# Hotec_H-bridge.net
KiCad netlist of a schematic drawn in EAGLE
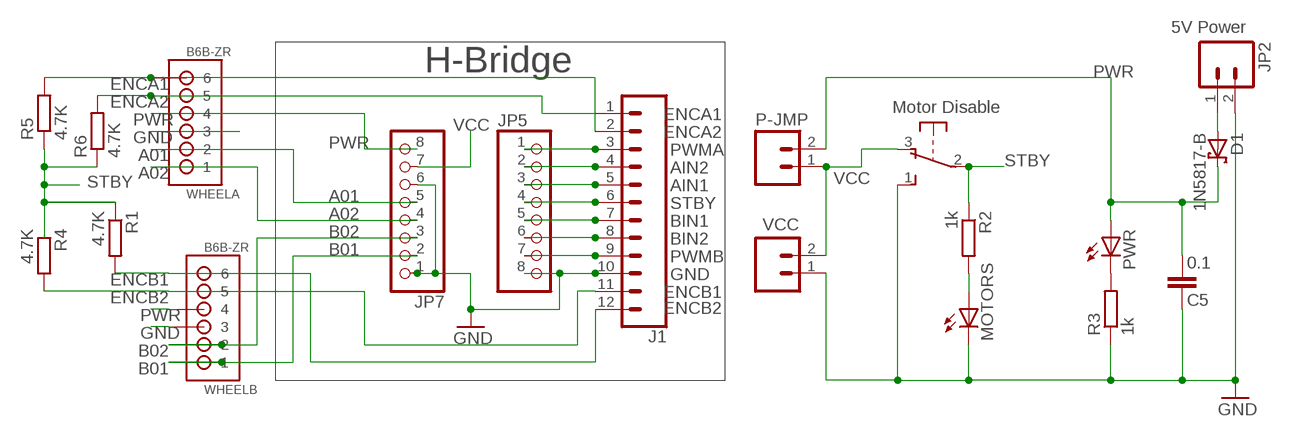
[diagram p0: schematic, sheet 1]

(export (version "E")
  (design (tool "Eeschema 10.0.6"))
  (components
    (comp (ref "C5")
      (value "0.1")
      (footprint "eagle-import:CAP-PTH-SMALLEZ")
      (libsource (lib "eagle-import") (part "CAPEZ"))
    )
    (comp (ref "D1")
      (value "1N5817-B")
      (footprint "eagle-import:DO41-7.6")
      (libsource (lib "eagle-import") (part "1N5817-B"))
    )
    (comp (ref "J1")
      (value "CONN_12")
      (footprint "eagle-import:1X12")
      (libsource (lib "eagle-import") (part "CONN_12"))
    )
    (comp (ref "JP2")
      (value "M023.5MM")
      (footprint "eagle-import:SCREWTERMINAL-3.5MM-2")
      (libsource (lib "eagle-import") (part "M023.5MM"))
    )
    (comp (ref "JP5")
      (value "PINHD-1X8CLEANBIG")
      (footprint "eagle-import:1X08-CLEANBIG")
      (libsource (lib "eagle-import") (part "PINHD-1X8CLEANBIG"))
    )
    (comp (ref "JP7")
      (value "PINHD-1X8CLEANBIG")
      (footprint "eagle-import:1X08-CLEANBIG")
      (libsource (lib "eagle-import") (part "PINHD-1X8CLEANBIG"))
    )
    (comp (ref "MOTORS")
      (value "LED3MM")
      (footprint "eagle-import:LED3MM")
      (libsource (lib "eagle-import") (part "LED3MM"))
    )
    (comp (ref "P-JMP")
      (value "M02PTH")
      (footprint "eagle-import:1X02")
      (libsource (lib "eagle-import") (part "M02PTH"))
    )
    (comp (ref "PWR")
      (value "LED3MM")
      (footprint "eagle-import:LED3MM")
      (libsource (lib "eagle-import") (part "LED3MM"))
    )
    (comp (ref "R1")
      (value "4.7K")
      (footprint "eagle-import:0204_7")
      (libsource (lib "eagle-import") (part "R-EU_0204/7"))
    )
    (comp (ref "R2")
      (value "1k")
      (footprint "eagle-import:0204_7")
      (libsource (lib "eagle-import") (part "R-EU_0204/7"))
    )
    (comp (ref "R3")
      (value "1k")
      (footprint "eagle-import:0204_7")
      (libsource (lib "eagle-import") (part "R-EU_0204/7"))
    )
    (comp (ref "R4")
      (value "4.7K")
      (footprint "eagle-import:0204_7")
      (libsource (lib "eagle-import") (part "R-EU_0204/7"))
    )
    (comp (ref "R5")
      (value "4.7K")
      (footprint "eagle-import:0204_7")
      (libsource (lib "eagle-import") (part "R-EU_0204/7"))
    )
    (comp (ref "R6")
      (value "4.7K")
      (footprint "eagle-import:0204_7")
      (libsource (lib "eagle-import") (part "R-EU_0204/7"))
    )
    (comp (ref "SW1")
      (value "OS102011MA1Q")
      (footprint "eagle-import:OS102011MA1Q")
      (libsource (lib "eagle-import") (part "OS102011MA1Q"))
    )
    (comp (ref "VCC")
      (value "M02PTH")
      (footprint "eagle-import:1X02")
      (libsource (lib "eagle-import") (part "M02PTH"))
    )
    (comp (ref "WHEELA")
      (value "B6B-ZR")
      (footprint "eagle-import:B6B-ZR")
      (libsource (lib "eagle-import") (part "B6B-ZR"))
    )
    (comp (ref "WHEELB")
      (value "B6B-ZR")
      (footprint "eagle-import:B6B-ZR")
      (libsource (lib "eagle-import") (part "B6B-ZR"))
    )
  )
  (nets
    (net (code "1") (name "/A01") (class "Default")
      (node (ref "JP7") (pin "5") (pinfunction "5_5") (pintype "passive"))
      (node (ref "WHEELA") (pin "2") (pinfunction "2_2") (pintype "bidirectional"))
    )
    (net (code "2") (name "/A02") (class "Default")
      (node (ref "JP7") (pin "4") (pinfunction "4_4") (pintype "passive"))
      (node (ref "WHEELA") (pin "1") (pinfunction "1_1") (pintype "bidirectional"))
    )
    (net (code "3") (name "/AIN1") (class "Default")
      (node (ref "J1") (pin "5") (pinfunction "5_5") (pintype "passive"))
      (node (ref "JP5") (pin "3") (pinfunction "3_3") (pintype "passive"))
    )
    (net (code "4") (name "/AIN2") (class "Default")
      (node (ref "J1") (pin "4") (pinfunction "4_4") (pintype "passive"))
      (node (ref "JP5") (pin "2") (pinfunction "2_2") (pintype "passive"))
    )
    (net (code "5") (name "/B01") (class "Default")
      (node (ref "JP7") (pin "2") (pinfunction "2_2") (pintype "passive"))
      (node (ref "WHEELB") (pin "1") (pinfunction "1_1") (pintype "bidirectional"))
    )
    (net (code "6") (name "/B02") (class "Default")
      (node (ref "JP7") (pin "3") (pinfunction "3_3") (pintype "passive"))
      (node (ref "WHEELB") (pin "2") (pinfunction "2_2") (pintype "bidirectional"))
    )
    (net (code "7") (name "/BIN1") (class "Default")
      (node (ref "J1") (pin "7") (pinfunction "7_7") (pintype "passive"))
      (node (ref "JP5") (pin "5") (pinfunction "5_5") (pintype "passive"))
    )
    (net (code "8") (name "/BIN2") (class "Default")
      (node (ref "J1") (pin "8") (pinfunction "8_8") (pintype "passive"))
      (node (ref "JP5") (pin "6") (pinfunction "6_6") (pintype "passive"))
    )
    (net (code "9") (name "/ENCA1") (class "Default")
      (node (ref "J1") (pin "2") (pinfunction "2_2") (pintype "passive"))
      (node (ref "R5") (pin "2") (pinfunction "2_2") (pintype "passive"))
      (node (ref "WHEELA") (pin "6") (pinfunction "6_6") (pintype "bidirectional"))
    )
    (net (code "10") (name "/ENCA2") (class "Default")
      (node (ref "J1") (pin "1") (pinfunction "1_1") (pintype "passive"))
      (node (ref "R6") (pin "2") (pinfunction "2_2") (pintype "passive"))
      (node (ref "WHEELA") (pin "5") (pinfunction "5_5") (pintype "bidirectional"))
    )
    (net (code "11") (name "/ENCB1") (class "Default")
      (node (ref "J1") (pin "12") (pinfunction "12_12") (pintype "passive"))
      (node (ref "R1") (pin "2") (pinfunction "2_2") (pintype "passive"))
      (node (ref "WHEELB") (pin "6") (pinfunction "6_6") (pintype "bidirectional"))
    )
    (net (code "12") (name "/ENCB2") (class "Default")
      (node (ref "J1") (pin "11") (pinfunction "11_11") (pintype "passive"))
      (node (ref "R4") (pin "2") (pinfunction "2_2") (pintype "passive"))
      (node (ref "WHEELB") (pin "5") (pinfunction "5_5") (pintype "bidirectional"))
    )
    (net (code "13") (name "/PWMA") (class "Default")
      (node (ref "J1") (pin "3") (pinfunction "3_3") (pintype "passive"))
      (node (ref "JP5") (pin "1") (pinfunction "1_1") (pintype "passive"))
    )
    (net (code "14") (name "/PWMB") (class "Default")
      (node (ref "J1") (pin "9") (pinfunction "9_9") (pintype "passive"))
      (node (ref "JP5") (pin "7") (pinfunction "7_7") (pintype "passive"))
    )
    (net (code "15") (name "/PWR") (class "Default")
      (node (ref "C5") (pin "2") (pinfunction "2_2") (pintype "passive"))
      (node (ref "D1") (pin "C") (pinfunction "C_C") (pintype "passive"))
      (node (ref "JP7") (pin "8") (pinfunction "8_8") (pintype "passive"))
      (node (ref "P-JMP") (pin "2") (pinfunction "2_2") (pintype "passive"))
      (node (ref "PWR") (pin "A") (pinfunction "A_A") (pintype "passive"))
      (node (ref "WHEELA") (pin "4") (pinfunction "4_4") (pintype "bidirectional"))
      (node (ref "WHEELB") (pin "4") (pinfunction "4_4") (pintype "bidirectional"))
    )
    (net (code "16") (name "/STBY") (class "Default")
      (node (ref "J1") (pin "6") (pinfunction "6_6") (pintype "passive"))
      (node (ref "JP5") (pin "4") (pinfunction "4_4") (pintype "passive"))
      (node (ref "R1") (pin "1") (pinfunction "1_1") (pintype "passive"))
      (node (ref "R2") (pin "1") (pinfunction "1_1") (pintype "passive"))
      (node (ref "R4") (pin "1") (pinfunction "1_1") (pintype "passive"))
      (node (ref "R5") (pin "1") (pinfunction "1_1") (pintype "passive"))
      (node (ref "R6") (pin "1") (pinfunction "1_1") (pintype "passive"))
      (node (ref "SW1") (pin "2") (pinfunction "P_2") (pintype "passive"))
    )
    (net (code "17") (name "/VCC") (class "Default")
      (node (ref "JP7") (pin "7") (pinfunction "7_7") (pintype "passive"))
      (node (ref "P-JMP") (pin "1") (pinfunction "1_1") (pintype "passive"))
      (node (ref "SW1") (pin "3") (pinfunction "O_3") (pintype "passive"))
      (node (ref "VCC") (pin "2") (pinfunction "2_2") (pintype "passive"))
    )
    (net (code "18") (name "GND") (class "Default")
      (node (ref "C5") (pin "1") (pinfunction "1_1") (pintype "passive"))
      (node (ref "J1") (pin "10") (pinfunction "10_10") (pintype "passive"))
      (node (ref "JP2") (pin "2") (pinfunction "2_2") (pintype "passive"))
      (node (ref "JP5") (pin "8") (pinfunction "8_8") (pintype "passive"))
      (node (ref "JP7") (pin "1") (pinfunction "1_1") (pintype "passive"))
      (node (ref "JP7") (pin "6") (pinfunction "6_6") (pintype "passive"))
      (node (ref "MOTORS") (pin "K") (pinfunction "C_K") (pintype "passive"))
      (node (ref "R3") (pin "1") (pinfunction "1_1") (pintype "passive"))
      (node (ref "SW1") (pin "1") (pinfunction "S_1") (pintype "passive"))
      (node (ref "VCC") (pin "1") (pinfunction "1_1") (pintype "passive"))
      (node (ref "WHEELA") (pin "3") (pinfunction "3_3") (pintype "bidirectional"))
      (node (ref "WHEELB") (pin "3") (pinfunction "3_3") (pintype "bidirectional"))
    )
    (net (code "19") (name "Net-(D1-PadA)") (class "Default")
      (node (ref "D1") (pin "A") (pinfunction "A_A") (pintype "passive"))
      (node (ref "JP2") (pin "1") (pinfunction "1_1") (pintype "passive"))
    )
    (net (code "20") (name "Net-(MOTORS-PadA)") (class "Default")
      (node (ref "MOTORS") (pin "A") (pinfunction "A_A") (pintype "passive"))
      (node (ref "R2") (pin "2") (pinfunction "2_2") (pintype "passive"))
    )
    (net (code "21") (name "Net-(PWR-C)") (class "Default")
      (node (ref "PWR") (pin "K") (pinfunction "C_K") (pintype "passive"))
      (node (ref "R3") (pin "2") (pinfunction "2_2") (pintype "passive"))
    )
  )
)
